# Shield_Amir_3xA4988_V_2.net
KiCad netlist of a schematic drawn in EasyEDA
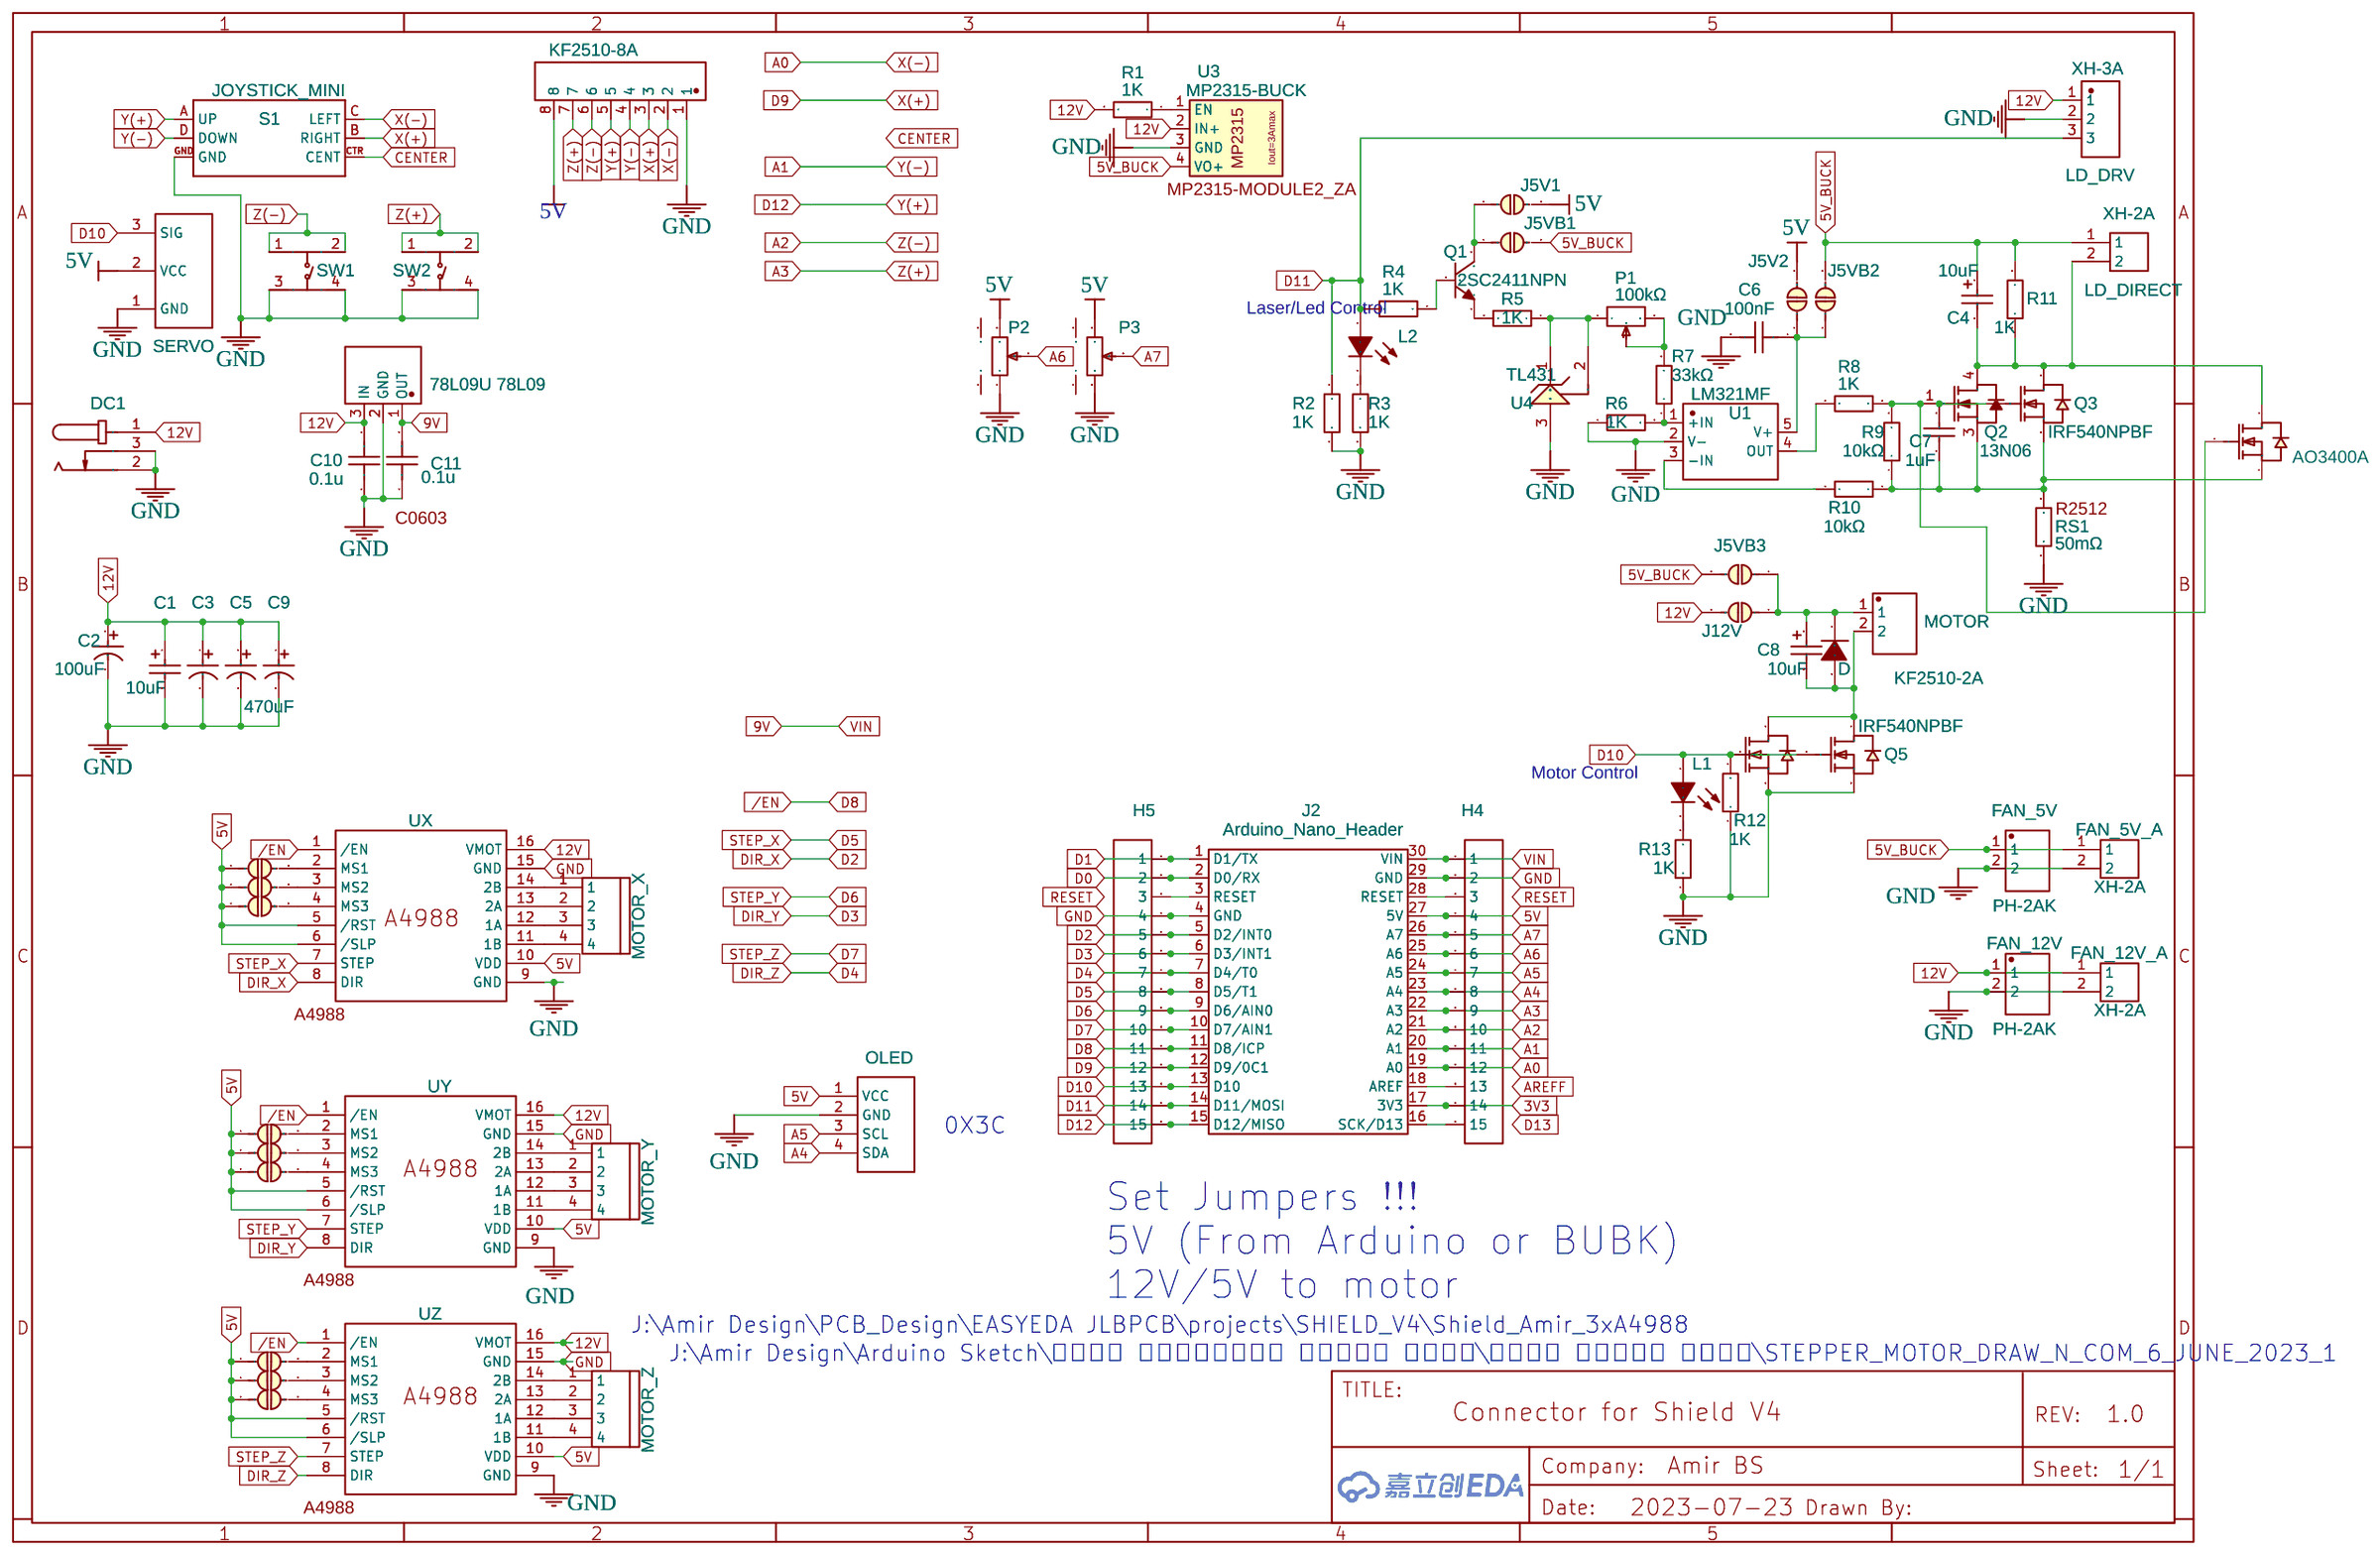
[diagram p0: schematic sheet]

(export (version "E")
  (design (tool "Eeschema 10.0.6"))
  (components
    (comp (ref "C1")
      (value "10uF")
      (fields (field (name "Manufacturer Part") "TAJA106K016RNJ") (field (name "Manufacturer") "Kyocera AVX"))
      (libsource (lib "") (part "TAJA106K016RNJ"))
    )
    (comp (ref "C2")
      (value "100uF")
      (fields
        (field (name "Manufacturer Part") "KM107M035E11RR0VH2FP0")
        (field (name "Manufacturer") "CX(承兴)")
      )
      (libsource (lib "") (part "100uF 35V 6.3*11"))
    )
    (comp (ref "C3")
      (value "470uF")
      (fields
        (field (name "Manufacturer Part") "GR477M025F12RR0VH4FP0")
        (field (name "Manufacturer") "CX(承兴)")
      )
      (libsource (lib "") (part "470uF 25V 8*12Black high frequency"))
    )
    (comp (ref "C4")
      (value "10uF")
      (fields (field (name "Manufacturer Part") "TAJA106K016RNJ") (field (name "Manufacturer") "Kyocera AVX"))
      (libsource (lib "") (part "TAJA106K016RNJ"))
    )
    (comp (ref "C5")
      (value "470uF")
      (fields
        (field (name "Manufacturer Part") "GR477M025F12RR0VH4FP0")
        (field (name "Manufacturer") "CX(承兴)")
      )
      (libsource (lib "") (part "470uF 25V 8*12Black high frequency"))
    )
    (comp (ref "C6")
      (value "100nF")
      (fields
        (field (name "BOM_Manufacturer Part") "CC0603KRX7R9BB104")
        (field (name "BOM_Supplier Part") "C14663")
      )
      (libsource (lib "") (part "CC0603KRX7R9BB104"))
    )
    (comp (ref "C7")
      (value "1uF")
      (fields
        (field (name "Manufacturer Part") "CL10A105KB8NNNC")
        (field (name "Manufacturer") "SAMSUNG(三星)")
      )
      (libsource (lib "") (part "CL10A105KB8NNNC"))
    )
    (comp (ref "C8")
      (value "10uF")
      (fields (field (name "Manufacturer Part") "TAJA106K016RNJ") (field (name "Manufacturer") "Kyocera AVX"))
      (libsource (lib "") (part "TAJA106K016RNJ"))
    )
    (comp (ref "C9")
      (value "470uF")
      (fields
        (field (name "Manufacturer Part") "GR477M025F12RR0VH4FP0")
        (field (name "Manufacturer") "CX(承兴)")
      )
      (libsource (lib "") (part "470uF 25V 8*12Black high frequency"))
    )
    (comp (ref "C10") (value "0.1u") (libsource (lib "") (part "C_0603_US")))
    (comp (ref "C11") (value "0.1u") (libsource (lib "") (part "C_0603_US_1")))
    (comp (ref "CN2")
      (value "KF2510-8A")
      (fields (field (name "Manufacturer Part") "2510-8A") (field (name "Manufacturer") "BOOMELE(博穆精密)"))
      (libsource (lib "") (part "KF2510-8A"))
    )
    (comp (ref "D")
      (value "1N4007")
      (fields (field (name "BOM_Manufacturer Part") "1N4007F") (field (name "BOM_Supplier Part") "C110856"))
      (libsource (lib "") (part "1N4007F"))
    )
    (comp (ref "DC1")
      (value "DC")
      (fields
        (field (name "BOM_Manufacturer Part") "DC005-2.0MM")
        (field (name "BOM_Supplier Part") "C111567")
      )
      (libsource (lib "") (part "DC005-2.0MM"))
    )
    (comp (ref "FAN_5V")
      (value "PH-2AK")
      (fields (field (name "BOM_Supplier Part") "C8886"))
      (libsource (lib "") (part "PH-2AK_1"))
    )
    (comp (ref "FAN_5V_A")
      (value "XH-2A")
      (fields (field (name "Manufacturer") "BOOMELE(博穆精密)"))
      (libsource (lib "") (part "XH-2A"))
    )
    (comp (ref "FAN_12V")
      (value "PH-2AK")
      (fields (field (name "BOM_Supplier Part") "C8886"))
      (libsource (lib "") (part "PH-2AK"))
    )
    (comp (ref "FAN_12V_A")
      (value "XH-2A")
      (fields (field (name "Manufacturer") "BOOMELE(博穆精密)"))
      (libsource (lib "") (part "XH-2A_1"))
    )
    (comp (ref "H4")
      (value "HDR-F-2.54_1x15")
      (fields (field (name "BOM_Supplier Part") "C124408"))
      (libsource (lib "") (part "HDR-F-2.54_1x15_1"))
    )
    (comp (ref "H5")
      (value "HDR-F-2.54_1x15")
      (fields (field (name "BOM_Supplier Part") "C124408"))
      (libsource (lib "") (part "HDR-F-2.54_1x15"))
    )
    (comp (ref "J2") (value "Arduino_Nano_Header") (libsource (lib "") (part "Arduino_Nano_Header")))
    (comp (ref "J5V1") (value "JUMPER-SMT_2") (libsource (lib "") (part "JUMPER-SMT_2_1")))
    (comp (ref "J5V2") (value "JUMPER-SMT_2") (libsource (lib "") (part "JUMPER-SMT_2_4")))
    (comp (ref "J5VB1") (value "JUMPER-SMT_2") (libsource (lib "") (part "JUMPER-SMT_2_5")))
    (comp (ref "J5VB2") (value "JUMPER-SMT_2") (libsource (lib "") (part "JUMPER-SMT_2_8")))
    (comp (ref "J5VB3") (value "JUMPER-SMT_2") (libsource (lib "") (part "JUMPER-SMT_2_7")))
    (comp (ref "J12V") (value "JUMPER-SMT_2") (libsource (lib "") (part "JUMPER-SMT_2_2")))
    (comp (ref "JX1") (value "JUMPER-SMT_2") (libsource (lib "") (part "JUMPER-SMT_2_3")))
    (comp (ref "JX2") (value "JUMPER-SMT_2") (libsource (lib "") (part "JUMPER-SMT_2_3")))
    (comp (ref "JX3") (value "JUMPER-SMT_2") (libsource (lib "") (part "JUMPER-SMT_2_3")))
    (comp (ref "JY1") (value "JUMPER-SMT_2") (libsource (lib "") (part "JUMPER-SMT_2_6")))
    (comp (ref "JY2") (value "JUMPER-SMT_2") (libsource (lib "") (part "JUMPER-SMT_2_6")))
    (comp (ref "JY3") (value "JUMPER-SMT_2") (libsource (lib "") (part "JUMPER-SMT_2_6")))
    (comp (ref "JZ1") (value "JUMPER-SMT_2") (libsource (lib "") (part "JUMPER-SMT_2")))
    (comp (ref "JZ2") (value "JUMPER-SMT_2") (libsource (lib "") (part "JUMPER-SMT_2")))
    (comp (ref "JZ3") (value "JUMPER-SMT_2") (libsource (lib "") (part "JUMPER-SMT_2")))
    (comp (ref "L1")
      (value "LED")
      (fields
        (field (name "BOM_Manufacturer Part") "19-217/BHC-ZL1M2RY/3T")
        (field (name "BOM_Supplier Part") "C72041")
      )
      (libsource (lib "") (part "19-217/BHC-ZL1M2RY/3T"))
    )
    (comp (ref "L2")
      (value "LED")
      (fields
        (field (name "BOM_Manufacturer Part") "19-217/BHC-ZL1M2RY/3T")
        (field (name "BOM_Supplier Part") "C72041")
      )
      (libsource (lib "") (part "19-217/BHC-ZL1M2RY/3T"))
    )
    (comp (ref "LD_DIRECT")
      (value "XH-2A")
      (fields (field (name "Manufacturer") "BOOMELE(博穆精密)"))
      (libsource (lib "") (part "XH-2A_2"))
    )
    (comp (ref "LD_DRV")
      (value "XH-3A")
      (fields (field (name "Manufacturer") "HCTL(华灿天禄)"))
      (libsource (lib "") (part "XH-3A_C2908601"))
    )
    (comp (ref "MOTOR")
      (value "KF2510-2A")
      (fields (field (name "BOM_Supplier Part") "C27543"))
      (libsource (lib "") (part "KF2510-2A"))
    )
    (comp (ref "MOTOR_X")
      (value "XH2.54-4AW")
      (fields (field (name "Manufacturer Part") "XH-4AW") (field (name "Manufacturer") "BOOMELE(博穆精密)"))
      (libsource (lib "") (part "XH2.54-4AW_2"))
    )
    (comp (ref "MOTOR_Y")
      (value "XH2.54-4AW")
      (fields (field (name "Manufacturer Part") "XH-4AW") (field (name "Manufacturer") "BOOMELE(博穆精密)"))
      (libsource (lib "") (part "XH2.54-4AW"))
    )
    (comp (ref "MOTOR_Z")
      (value "XH2.54-4AW")
      (fields (field (name "Manufacturer Part") "XH-4AW") (field (name "Manufacturer") "BOOMELE(博穆精密)"))
      (libsource (lib "") (part "XH2.54-4AW_1"))
    )
    (comp (ref "OLED")
      (value "1.3 inch OLED SSH1106 I2C 128x64 copy")
      (libsource (lib "") (part "1.3 inch OLED SSH1106 I2C 128x64 copy"))
    )
    (comp (ref "P1")
      (value "100kΩ")
      (fields (field (name "Manufacturer Part") "3296W-1-104LF") (field (name "Manufacturer") "BOURNS"))
      (libsource (lib "") (part "3296W-1-104LF"))
    )
    (comp (ref "P2")
      (value "长柄旋转电位器")
      (fields (field (name "BOM_Supplier Part") "C2874842"))
      (libsource (lib "") (part "长柄旋转电位器"))
    )
    (comp (ref "P3")
      (value "长柄旋转电位器")
      (fields (field (name "BOM_Supplier Part") "C2874842"))
      (libsource (lib "") (part "长柄旋转电位器"))
    )
    (comp (ref "Q1")
      (value "2SC2411NPN")
      (fields (field (name "Manufacturer Part") "2SC2411KT146R") (field (name "Manufacturer") "ROHM(罗姆)"))
      (libsource (lib "") (part "2SC2411KT146R"))
    )
    (comp (ref "Q2")
      (value "13N06")
      (fields (field (name "Manufacturer Part") "FQD13N06LTM") (field (name "Manufacturer") "onsemi(安森美)"))
      (libsource (lib "") (part "FQD13N06LTM"))
    )
    (comp (ref "Q3")
      (value "IRF540NPBF")
      (fields (field (name "Manufacturer") "Infineon(英飞凌)"))
      (libsource (lib "") (part "IRF540NPBF"))
    )
    (comp (ref "Q4")
      (value "Q")
      (fields (field (name "BOM_Manufacturer Part") "JSM2302") (field (name "BOM_Supplier Part") "C916403"))
      (libsource (lib "") (part "JSM2302"))
    )
    (comp (ref "Q5")
      (value "IRF540NPBF")
      (fields (field (name "Manufacturer") "Infineon(英飞凌)"))
      (libsource (lib "") (part "IRF540NPBF"))
    )
    (comp (ref "Q6")
      (value "AO3400A")
      (fields (field (name "Manufacturer") "AOS"))
      (libsource (lib "") (part "AO3400A"))
    )
    (comp (ref "R1")
      (value "1K")
      (fields
        (field (name "BOM_Manufacturer Part") "0603WAF1001T5E")
        (field (name "BOM_Supplier Part") "C21190")
      )
      (libsource (lib "") (part "0603WAF1001T5E_3"))
    )
    (comp (ref "R2")
      (value "1K")
      (fields
        (field (name "BOM_Manufacturer Part") "0603WAF1001T5E")
        (field (name "BOM_Supplier Part") "C21190")
      )
      (libsource (lib "") (part "0603WAF1001T5E_1"))
    )
    (comp (ref "R3")
      (value "1K")
      (fields
        (field (name "BOM_Manufacturer Part") "0603WAF1001T5E")
        (field (name "BOM_Supplier Part") "C21190")
      )
      (libsource (lib "") (part "0603WAF1001T5E_1"))
    )
    (comp (ref "R4")
      (value "1K")
      (fields
        (field (name "BOM_Manufacturer Part") "0603WAF1001T5E")
        (field (name "BOM_Supplier Part") "C21190")
      )
      (libsource (lib "") (part "0603WAF1001T5E"))
    )
    (comp (ref "R5")
      (value "1K")
      (fields
        (field (name "BOM_Manufacturer Part") "0603WAF1001T5E")
        (field (name "BOM_Supplier Part") "C21190")
      )
      (libsource (lib "") (part "0603WAF1001T5E_3"))
    )
    (comp (ref "R6")
      (value "1K")
      (fields
        (field (name "BOM_Manufacturer Part") "0603WAF1001T5E")
        (field (name "BOM_Supplier Part") "C21190")
      )
      (libsource (lib "") (part "0603WAF1001T5E"))
    )
    (comp (ref "R7")
      (value "33kΩ")
      (fields
        (field (name "Manufacturer Part") "0603WAF3302T5E")
        (field (name "Manufacturer") "UNI-ROYAL(厚声)")
      )
      (libsource (lib "") (part "0603WAF3302T5E"))
    )
    (comp (ref "R8")
      (value "1K")
      (fields
        (field (name "BOM_Manufacturer Part") "0603WAF1001T5E")
        (field (name "BOM_Supplier Part") "C21190")
      )
      (libsource (lib "") (part "0603WAF1001T5E_3"))
    )
    (comp (ref "R9")
      (value "10kΩ")
      (fields
        (field (name "BOM_Manufacturer Part") "0603WAF1002T5E")
        (field (name "BOM_Supplier Part") "C25804")
      )
      (libsource (lib "") (part "0603WAF1002T5E_1"))
    )
    (comp (ref "R10")
      (value "10kΩ")
      (fields
        (field (name "BOM_Manufacturer Part") "0603WAF1002T5E")
        (field (name "BOM_Supplier Part") "C25804")
      )
      (libsource (lib "") (part "0603WAF1002T5E"))
    )
    (comp (ref "R11")
      (value "1K")
      (fields
        (field (name "BOM_Manufacturer Part") "0603WAF1001T5E")
        (field (name "BOM_Supplier Part") "C21190")
      )
      (libsource (lib "") (part "0603WAF1001T5E_2"))
    )
    (comp (ref "R12")
      (value "1K")
      (fields
        (field (name "BOM_Manufacturer Part") "0603WAF1001T5E")
        (field (name "BOM_Supplier Part") "C21190")
      )
      (libsource (lib "") (part "0603WAF1001T5E_2"))
    )
    (comp (ref "R13")
      (value "1K")
      (fields
        (field (name "BOM_Manufacturer Part") "0603WAF1001T5E")
        (field (name "BOM_Supplier Part") "C21190")
      )
      (libsource (lib "") (part "0603WAF1001T5E_2"))
    )
    (comp (ref "RS1")
      (value "50mΩ")
      (fields
        (field (name "Manufacturer Part") "CR2512FR050E04R")
        (field (name "Manufacturer") "EVER OHMS(天二科技)")
      )
      (libsource (lib "") (part "CR2512F0R05E04"))
    )
    (comp (ref "S1") (value "JOYSTICK_MINI") (libsource (lib "") (part "JOYSTICK_MINI")))
    (comp (ref "SERVO")
      (value "Servo+3d")
      (fields (field (name "BOM_Manufacturer Part") "New SchematicLib"))
      (libsource (lib "") (part "Servo+3d"))
    )
    (comp (ref "SW1")
      (value "TC-6610-7-160G")
      (fields (field (name "Manufacturer") "HCTL(华灿天禄)"))
      (libsource (lib "") (part "TC-6610-7-160G"))
    )
    (comp (ref "SW2")
      (value "TC-6610-7-160G")
      (fields (field (name "Manufacturer") "HCTL(华灿天禄)"))
      (libsource (lib "") (part "TC-6610-7-160G"))
    )
    (comp (ref "U1")
      (value "LM321MF")
      (fields (field (name "Manufacturer") "UMW(广东友台半导体)"))
      (libsource (lib "") (part "LM321MF"))
    )
    (comp (ref "U3") (value "MP2315-BUCK") (libsource (lib "") (part "MP2315-BUCK")))
    (comp (ref "U4")
      (value "TL431")
      (fields (field (name "Manufacturer Part") "TL431BIDBZR") (field (name "Manufacturer") "TI(德州仪器)"))
      (libsource (lib "") (part "TL431BIDBZR"))
    )
    (comp (ref "U5")
      (value "78L09U 78L09")
      (fields (field (name "Manufacturer") "CBI(创基)"))
      (libsource (lib "") (part "78L09U 78L09"))
    )
    (comp (ref "UX") (value "A4988") (libsource (lib "") (part "A4988")))
    (comp (ref "UY") (value "A4988") (libsource (lib "") (part "A4988_1")))
    (comp (ref "UZ") (value "A4988") (libsource (lib "") (part "A4988_2")))
  )
  (nets
    (net (code "1") (name "3V3") (class "Default")
      (node (ref "H4") (pin "14") (pinfunction "14_14") (pintype "unspecified"))
      (node (ref "J2") (pin "17") (pinfunction "3V3_17") (pintype "unspecified"))
    )
    (net (code "2") (name "5V") (class "Default")
      (node (ref "CN2") (pin "8") (pinfunction "8_8") (pintype "unspecified"))
      (node (ref "H4") (pin "4") (pinfunction "4_4") (pintype "unspecified"))
      (node (ref "J2") (pin "27") (pinfunction "5V_27") (pintype "unspecified"))
      (node (ref "J5V1") (pin "2") (pinfunction "2_2") (pintype "bidirectional"))
      (node (ref "J5V2") (pin "2") (pinfunction "2_2") (pintype "bidirectional"))
      (node (ref "JX1") (pin "1") (pinfunction "1_1") (pintype "bidirectional"))
      (node (ref "JX2") (pin "1") (pinfunction "1_1") (pintype "bidirectional"))
      (node (ref "JX3") (pin "1") (pinfunction "1_1") (pintype "bidirectional"))
      (node (ref "JY1") (pin "1") (pinfunction "1_1") (pintype "bidirectional"))
      (node (ref "JY2") (pin "1") (pinfunction "1_1") (pintype "bidirectional"))
      (node (ref "JY3") (pin "1") (pinfunction "1_1") (pintype "bidirectional"))
      (node (ref "JZ1") (pin "1") (pinfunction "1_1") (pintype "bidirectional"))
      (node (ref "JZ2") (pin "1") (pinfunction "1_1") (pintype "bidirectional"))
      (node (ref "JZ3") (pin "1") (pinfunction "1_1") (pintype "bidirectional"))
      (node (ref "OLED") (pin "1") (pinfunction "VCC_1") (pintype "passive"))
      (node (ref "P2") (pin "3") (pinfunction "3_3") (pintype "input"))
      (node (ref "P3") (pin "3") (pinfunction "3_3") (pintype "input"))
      (node (ref "SERVO") (pin "2") (pinfunction "VCC_2") (pintype "unspecified"))
      (node (ref "UX") (pin "10") (pinfunction "VDD_10") (pintype "unspecified"))
      (node (ref "UX") (pin "5") (pinfunction "/RST_5") (pintype "unspecified"))
      (node (ref "UX") (pin "6") (pinfunction "/SLP_6") (pintype "unspecified"))
      (node (ref "UY") (pin "10") (pinfunction "VDD_10") (pintype "unspecified"))
      (node (ref "UY") (pin "5") (pinfunction "/RST_5") (pintype "unspecified"))
      (node (ref "UY") (pin "6") (pinfunction "/SLP_6") (pintype "unspecified"))
      (node (ref "UZ") (pin "10") (pinfunction "VDD_10") (pintype "unspecified"))
      (node (ref "UZ") (pin "5") (pinfunction "/RST_5") (pintype "unspecified"))
      (node (ref "UZ") (pin "6") (pinfunction "/SLP_6") (pintype "unspecified"))
    )
    (net (code "3") (name "5V_BUCK") (class "Default")
      (node (ref "C4") (pin "1") (pinfunction "1_1") (pintype "input"))
      (node (ref "FAN_5V") (pin "1") (pinfunction "1_1") (pintype "unspecified"))
      (node (ref "FAN_5V_A") (pin "1") (pinfunction "1_1") (pintype "unspecified"))
      (node (ref "J5VB1") (pin "2") (pinfunction "2_2") (pintype "bidirectional"))
      (node (ref "J5VB2") (pin "2") (pinfunction "2_2") (pintype "bidirectional"))
      (node (ref "J5VB3") (pin "2") (pinfunction "2_2") (pintype "bidirectional"))
      (node (ref "LD_DIRECT") (pin "1") (pinfunction "1_1") (pintype "unspecified"))
      (node (ref "R11") (pin "2") (pinfunction "2_2") (pintype "input"))
      (node (ref "U3") (pin "4") (pinfunction "VO+_4") (pintype "unspecified"))
    )
    (net (code "4") (name "9V") (class "Default")
      (node (ref "C11") (pin "2") (pinfunction "2_2") (pintype "unspecified"))
      (node (ref "H4") (pin "1") (pinfunction "1_1") (pintype "unspecified"))
      (node (ref "J2") (pin "30") (pinfunction "VIN_30") (pintype "unspecified"))
      (node (ref "U5") (pin "1") (pinfunction "OUT_1") (pintype "unspecified"))
    )
    (net (code "5") (name "12V") (class "Default")
      (node (ref "C1") (pin "1") (pinfunction "1_1") (pintype "input"))
      (node (ref "C10") (pin "2") (pinfunction "2_2") (pintype "unspecified"))
      (node (ref "C2") (pin "1") (pinfunction "1_1") (pintype "input"))
      (node (ref "C3") (pin "1") (pinfunction "1_1") (pintype "input"))
      (node (ref "C5") (pin "1") (pinfunction "1_1") (pintype "input"))
      (node (ref "C9") (pin "1") (pinfunction "1_1") (pintype "input"))
      (node (ref "DC1") (pin "1") (pinfunction "1_1") (pintype "unspecified"))
      (node (ref "FAN_12V") (pin "1") (pinfunction "1_1") (pintype "unspecified"))
      (node (ref "FAN_12V_A") (pin "1") (pinfunction "1_1") (pintype "unspecified"))
      (node (ref "J12V") (pin "2") (pinfunction "2_2") (pintype "bidirectional"))
      (node (ref "LD_DRV") (pin "1") (pinfunction "1_1") (pintype "unspecified"))
      (node (ref "R1") (pin "2") (pinfunction "2_2") (pintype "input"))
      (node (ref "U3") (pin "2") (pinfunction "IN+_2") (pintype "unspecified"))
      (node (ref "U5") (pin "3") (pinfunction "IN_3") (pintype "unspecified"))
      (node (ref "UX") (pin "16") (pinfunction "VMOT_16") (pintype "unspecified"))
      (node (ref "UY") (pin "16") (pinfunction "VMOT_16") (pintype "unspecified"))
      (node (ref "UZ") (pin "16") (pinfunction "VMOT_16") (pintype "unspecified"))
    )
    (net (code "6") (name "A0") (class "Default")
      (node (ref "CN2") (pin "2") (pinfunction "2_2") (pintype "unspecified"))
      (node (ref "H4") (pin "12") (pinfunction "12_12") (pintype "unspecified"))
      (node (ref "J2") (pin "19") (pinfunction "A0_19") (pintype "unspecified"))
      (node (ref "S1") (pin "C") (pinfunction "LEFT_C") (pintype "unspecified"))
    )
    (net (code "7") (name "A1") (class "Default")
      (node (ref "CN2") (pin "4") (pinfunction "4_4") (pintype "unspecified"))
      (node (ref "H4") (pin "11") (pinfunction "11_11") (pintype "unspecified"))
      (node (ref "J2") (pin "20") (pinfunction "A1_20") (pintype "unspecified"))
      (node (ref "S1") (pin "D") (pinfunction "DOWN_D") (pintype "unspecified"))
    )
    (net (code "8") (name "A2") (class "Default")
      (node (ref "CN2") (pin "6") (pinfunction "6_6") (pintype "unspecified"))
      (node (ref "H4") (pin "10") (pinfunction "10_10") (pintype "unspecified"))
      (node (ref "J2") (pin "21") (pinfunction "A2_21") (pintype "unspecified"))
      (node (ref "SW1") (pin "1") (pinfunction "1_1") (pintype "unspecified"))
      (node (ref "SW1") (pin "2") (pinfunction "2_2") (pintype "unspecified"))
    )
    (net (code "9") (name "A3") (class "Default")
      (node (ref "CN2") (pin "7") (pinfunction "7_7") (pintype "unspecified"))
      (node (ref "H4") (pin "9") (pinfunction "9_9") (pintype "unspecified"))
      (node (ref "J2") (pin "22") (pinfunction "A3_22") (pintype "unspecified"))
      (node (ref "SW2") (pin "1") (pinfunction "1_1") (pintype "unspecified"))
      (node (ref "SW2") (pin "2") (pinfunction "2_2") (pintype "unspecified"))
    )
    (net (code "10") (name "A4") (class "Default")
      (node (ref "H4") (pin "8") (pinfunction "8_8") (pintype "unspecified"))
      (node (ref "J2") (pin "23") (pinfunction "A4_23") (pintype "unspecified"))
      (node (ref "OLED") (pin "4") (pinfunction "SDA_4") (pintype "bidirectional"))
    )
    (net (code "11") (name "A5") (class "Default")
      (node (ref "H4") (pin "7") (pinfunction "7_7") (pintype "unspecified"))
      (node (ref "J2") (pin "24") (pinfunction "A5_24") (pintype "unspecified"))
      (node (ref "OLED") (pin "3") (pinfunction "SCL_3") (pintype "bidirectional"))
    )
    (net (code "12") (name "A6") (class "Default")
      (node (ref "H4") (pin "6") (pinfunction "6_6") (pintype "unspecified"))
      (node (ref "J2") (pin "25") (pinfunction "A6_25") (pintype "unspecified"))
      (node (ref "P2") (pin "2") (pinfunction "2_2") (pintype "input"))
    )
    (net (code "13") (name "A7") (class "Default")
      (node (ref "H4") (pin "5") (pinfunction "5_5") (pintype "unspecified"))
      (node (ref "J2") (pin "26") (pinfunction "A7_26") (pintype "unspecified"))
      (node (ref "P3") (pin "2") (pinfunction "2_2") (pintype "input"))
    )
    (net (code "15") (name "CENTER") (class "Default")
      (node (ref "S1") (pin "CTR") (pinfunction "CENT_CTR") (pintype "unspecified"))
    )
    (net (code "16") (name "D0") (class "Default")
      (node (ref "H5") (pin "2") (pinfunction "2_2") (pintype "unspecified"))
      (node (ref "J2") (pin "2") (pinfunction "D0/RX_2") (pintype "unspecified"))
    )
    (net (code "17") (name "D1") (class "Default")
      (node (ref "H5") (pin "1") (pinfunction "1_1") (pintype "unspecified"))
      (node (ref "J2") (pin "1") (pinfunction "D1/TX_1") (pintype "unspecified"))
    )
    (net (code "18") (name "D2") (class "Default")
      (node (ref "H5") (pin "5") (pinfunction "5_5") (pintype "unspecified"))
      (node (ref "J2") (pin "5") (pinfunction "D2/INT0_5") (pintype "unspecified"))
      (node (ref "UX") (pin "8") (pinfunction "DIR_8") (pintype "unspecified"))
    )
    (net (code "19") (name "D3") (class "Default")
      (node (ref "H5") (pin "6") (pinfunction "6_6") (pintype "unspecified"))
      (node (ref "J2") (pin "6") (pinfunction "D3/INT1_6") (pintype "unspecified"))
      (node (ref "UY") (pin "8") (pinfunction "DIR_8") (pintype "unspecified"))
    )
    (net (code "20") (name "D4") (class "Default")
      (node (ref "H5") (pin "7") (pinfunction "7_7") (pintype "unspecified"))
      (node (ref "J2") (pin "7") (pinfunction "D4/T0_7") (pintype "unspecified"))
      (node (ref "UZ") (pin "8") (pinfunction "DIR_8") (pintype "unspecified"))
    )
    (net (code "21") (name "D5") (class "Default")
      (node (ref "H5") (pin "8") (pinfunction "8_8") (pintype "unspecified"))
      (node (ref "J2") (pin "8") (pinfunction "D5/T1_8") (pintype "unspecified"))
      (node (ref "UX") (pin "7") (pinfunction "STEP_7") (pintype "unspecified"))
    )
    (net (code "22") (name "D6") (class "Default")
      (node (ref "H5") (pin "9") (pinfunction "9_9") (pintype "unspecified"))
      (node (ref "J2") (pin "9") (pinfunction "D6/AIN0_9") (pintype "unspecified"))
      (node (ref "UY") (pin "7") (pinfunction "STEP_7") (pintype "unspecified"))
    )
    (net (code "23") (name "D7") (class "Default")
      (node (ref "H5") (pin "10") (pinfunction "10_10") (pintype "unspecified"))
      (node (ref "J2") (pin "10") (pinfunction "D7/AIN1_10") (pintype "unspecified"))
      (node (ref "UZ") (pin "7") (pinfunction "STEP_7") (pintype "unspecified"))
    )
    (net (code "24") (name "D8") (class "Default")
      (node (ref "H5") (pin "11") (pinfunction "11_11") (pintype "unspecified"))
      (node (ref "J2") (pin "11") (pinfunction "D8/ICP_11") (pintype "unspecified"))
      (node (ref "UX") (pin "1") (pinfunction "/EN_1") (pintype "unspecified"))
      (node (ref "UY") (pin "1") (pinfunction "/EN_1") (pintype "unspecified"))
      (node (ref "UZ") (pin "1") (pinfunction "/EN_1") (pintype "unspecified"))
    )
    (net (code "25") (name "D9") (class "Default")
      (node (ref "CN2") (pin "3") (pinfunction "3_3") (pintype "unspecified"))
      (node (ref "H5") (pin "12") (pinfunction "12_12") (pintype "unspecified"))
      (node (ref "J2") (pin "12") (pinfunction "D9/0C1_12") (pintype "unspecified"))
      (node (ref "S1") (pin "B") (pinfunction "RIGHT_B") (pintype "unspecified"))
    )
    (net (code "26") (name "D10") (class "Default")
      (node (ref "H5") (pin "13") (pinfunction "13_13") (pintype "unspecified"))
      (node (ref "J2") (pin "13") (pinfunction "D10_13") (pintype "unspecified"))
      (node (ref "L1") (pin "1") (pinfunction "A_1") (pintype "input"))
      (node (ref "Q4") (pin "1") (pinfunction "G_1") (pintype "unspecified"))
      (node (ref "Q5") (pin "1") (pinfunction "G_1") (pintype "unspecified"))
      (node (ref "R12") (pin "2") (pinfunction "2_2") (pintype "input"))
      (node (ref "SERVO") (pin "3") (pinfunction "SIG_3") (pintype "unspecified"))
    )
    (net (code "27") (name "D11") (class "Default")
      (node (ref "H5") (pin "14") (pinfunction "14_14") (pintype "unspecified"))
      (node (ref "J2") (pin "14") (pinfunction "D11/MOSI_14") (pintype "unspecified"))
      (node (ref "L2") (pin "1") (pinfunction "A_1") (pintype "input"))
      (node (ref "LD_DRV") (pin "3") (pinfunction "3_3") (pintype "unspecified"))
      (node (ref "R2") (pin "1") (pinfunction "1_1") (pintype "input"))
      (node (ref "R4") (pin "1") (pinfunction "1_1") (pintype "input"))
    )
    (net (code "28") (name "D12") (class "Default")
      (node (ref "CN2") (pin "5") (pinfunction "5_5") (pintype "unspecified"))
      (node (ref "H5") (pin "15") (pinfunction "15_15") (pintype "unspecified"))
      (node (ref "J2") (pin "15") (pinfunction "D12/MISO_15") (pintype "unspecified"))
      (node (ref "S1") (pin "A") (pinfunction "UP_A") (pintype "unspecified"))
    )
    (net (code "30") (name "GND") (class "Default")
      (node (ref "C1") (pin "2") (pinfunction "2_2") (pintype "input"))
      (node (ref "C10") (pin "1") (pinfunction "1_1") (pintype "unspecified"))
      (node (ref "C11") (pin "1") (pinfunction "1_1") (pintype "unspecified"))
      (node (ref "C2") (pin "2") (pinfunction "2_2") (pintype "input"))
      (node (ref "C3") (pin "2") (pinfunction "2_2") (pintype "input"))
      (node (ref "C5") (pin "2") (pinfunction "2_2") (pintype "input"))
      (node (ref "C6") (pin "2") (pinfunction "2_2") (pintype "unspecified"))
      (node (ref "C9") (pin "2") (pinfunction "2_2") (pintype "input"))
      (node (ref "CN2") (pin "1") (pinfunction "1_1") (pintype "unspecified"))
      (node (ref "DC1") (pin "2") (pinfunction "2_2") (pintype "unspecified"))
      (node (ref "DC1") (pin "3") (pinfunction "3_3") (pintype "unspecified"))
      (node (ref "FAN_12V") (pin "2") (pinfunction "2_2") (pintype "unspecified"))
      (node (ref "FAN_12V_A") (pin "2") (pinfunction "2_2") (pintype "unspecified"))
      (node (ref "FAN_5V") (pin "2") (pinfunction "2_2") (pintype "unspecified"))
      (node (ref "FAN_5V_A") (pin "2") (pinfunction "2_2") (pintype "unspecified"))
      (node (ref "H4") (pin "2") (pinfunction "2_2") (pintype "unspecified"))
      (node (ref "H5") (pin "4") (pinfunction "4_4") (pintype "unspecified"))
      (node (ref "J2") (pin "29") (pinfunction "GND_29") (pintype "unspecified"))
      (node (ref "J2") (pin "4") (pinfunction "GND_4") (pintype "unspecified"))
      (node (ref "LD_DRV") (pin "2") (pinfunction "2_2") (pintype "unspecified"))
      (node (ref "OLED") (pin "2") (pinfunction "GND_2") (pintype "passive"))
      (node (ref "P2") (pin "1") (pinfunction "1_1") (pintype "input"))
      (node (ref "P3") (pin "1") (pinfunction "1_1") (pintype "input"))
      (node (ref "Q4") (pin "2") (pinfunction "S_2") (pintype "unspecified"))
      (node (ref "Q5") (pin "3") (pinfunction "S_3") (pintype "unspecified"))
      (node (ref "R12") (pin "1") (pinfunction "1_1") (pintype "input"))
      (node (ref "R13") (pin "1") (pinfunction "1_1") (pintype "input"))
      (node (ref "R2") (pin "2") (pinfunction "2_2") (pintype "input"))
      (node (ref "R3") (pin "2") (pinfunction "2_2") (pintype "input"))
      (node (ref "R6") (pin "1") (pinfunction "1_1") (pintype "input"))
      (node (ref "RS1") (pin "1") (pinfunction "1_1") (pintype "unspecified"))
      (node (ref "S1") (pin "GND") (pinfunction "GND_GND") (pintype "unspecified"))
      (node (ref "SERVO") (pin "1") (pinfunction "GND_1") (pintype "unspecified"))
      (node (ref "SW1") (pin "3") (pinfunction "3_3") (pintype "unspecified"))
      (node (ref "SW1") (pin "4") (pinfunction "4_4") (pintype "unspecified"))
      (node (ref "SW2") (pin "3") (pinfunction "3_3") (pintype "unspecified"))
      (node (ref "SW2") (pin "4") (pinfunction "4_4") (pintype "unspecified"))
      (node (ref "U1") (pin "2") (pinfunction "V-_2") (pintype "unspecified"))
      (node (ref "U3") (pin "3") (pinfunction "GND_3") (pintype "unspecified"))
      (node (ref "U4") (pin "3") (pinfunction "ANODE_3") (pintype "unspecified"))
      (node (ref "U5") (pin "2") (pinfunction "GND_2") (pintype "unspecified"))
      (node (ref "UX") (pin "15") (pinfunction "GND_15") (pintype "unspecified"))
      (node (ref "UX") (pin "9") (pinfunction "GND_9") (pintype "unspecified"))
      (node (ref "UY") (pin "15") (pinfunction "GND_15") (pintype "unspecified"))
      (node (ref "UY") (pin "9") (pinfunction "GND_9") (pintype "unspecified"))
      (node (ref "UZ") (pin "15") (pinfunction "GND_15") (pintype "unspecified"))
      (node (ref "UZ") (pin "9") (pinfunction "GND_9") (pintype "unspecified"))
    )
    (net (code "31") (name "Net-(D-A)") (class "Default")
      (node (ref "C8") (pin "2") (pinfunction "2_2") (pintype "input"))
      (node (ref "D") (pin "2") (pinfunction "A_2") (pintype "unspecified"))
      (node (ref "MOTOR") (pin "2") (pinfunction "2_2") (pintype "unspecified"))
      (node (ref "Q4") (pin "3") (pinfunction "D_3") (pintype "unspecified"))
      (node (ref "Q5") (pin "2") (pinfunction "D_2") (pintype "unspecified"))
    )
    (net (code "32") (name "Net-(D-C)") (class "Default")
      (node (ref "C8") (pin "1") (pinfunction "1_1") (pintype "input"))
      (node (ref "D") (pin "1") (pinfunction "C_1") (pintype "unspecified"))
      (node (ref "J12V") (pin "1") (pinfunction "1_1") (pintype "bidirectional"))
      (node (ref "J5VB3") (pin "1") (pinfunction "1_1") (pintype "bidirectional"))
      (node (ref "MOTOR") (pin "1") (pinfunction "1_1") (pintype "unspecified"))
    )
    (net (code "33") (name "Net-(H4-Pad3)") (class "Default")
      (node (ref "H4") (pin "3") (pinfunction "3_3") (pintype "unspecified"))
      (node (ref "J2") (pin "28") (pinfunction "RESET_28") (pintype "unspecified"))
    )
    (net (code "34") (name "Net-(H5-Pad3)") (class "Default")
      (node (ref "H5") (pin "3") (pinfunction "3_3") (pintype "unspecified"))
      (node (ref "J2") (pin "3") (pinfunction "RESET_3") (pintype "unspecified"))
    )
    (net (code "35") (name "Net-(J2-AREF)") (class "Default")
      (node (ref "H4") (pin "13") (pinfunction "13_13") (pintype "unspecified"))
      (node (ref "J2") (pin "18") (pinfunction "AREF_18") (pintype "unspecified"))
    )
    (net (code "36") (name "Net-(J2-SCK{slash}D13)") (class "Default")
      (node (ref "H4") (pin "15") (pinfunction "15_15") (pintype "unspecified"))
      (node (ref "J2") (pin "16") (pinfunction "SCK/D13_16") (pintype "unspecified"))
    )
    (net (code "37") (name "Net-(L1-C)") (class "Default")
      (node (ref "L1") (pin "2") (pinfunction "C_2") (pintype "input"))
      (node (ref "R13") (pin "2") (pinfunction "2_2") (pintype "input"))
    )
    (net (code "38") (name "Net-(L2-C)") (class "Default")
      (node (ref "L2") (pin "2") (pinfunction "C_2") (pintype "input"))
      (node (ref "R3") (pin "1") (pinfunction "1_1") (pintype "input"))
    )
    (net (code "39") (name "Net-(P1-Pad2)") (class "Default")
      (node (ref "P1") (pin "2") (pinfunction "2_2") (pintype "input"))
      (node (ref "P1") (pin "3") (pinfunction "3_3") (pintype "input"))
      (node (ref "R7") (pin "2") (pinfunction "2_2") (pintype "input"))
    )
    (net (code "40") (name "Net-(Q1-B)") (class "Default")
      (node (ref "Q1") (pin "2") (pinfunction "B_2") (pintype "unspecified"))
      (node (ref "R4") (pin "2") (pinfunction "2_2") (pintype "input"))
    )
    (net (code "41") (name "Net-(Q1-C)") (class "Default")
      (node (ref "J5V1") (pin "1") (pinfunction "1_1") (pintype "bidirectional"))
      (node (ref "J5VB1") (pin "1") (pinfunction "1_1") (pintype "bidirectional"))
      (node (ref "Q1") (pin "3") (pinfunction "C_3") (pintype "unspecified"))
    )
    (net (code "42") (name "Net-(Q1-E)") (class "Default")
      (node (ref "Q1") (pin "1") (pinfunction "E_1") (pintype "unspecified"))
      (node (ref "R5") (pin "2") (pinfunction "2_2") (pintype "input"))
    )
    (net (code "43") (name "Net-(Q2-D)") (class "Default")
      (node (ref "C4") (pin "2") (pinfunction "2_2") (pintype "input"))
      (node (ref "LD_DIRECT") (pin "2") (pinfunction "2_2") (pintype "unspecified"))
      (node (ref "Q2") (pin "4") (pinfunction "D_4") (pintype "unspecified"))
      (node (ref "Q3") (pin "2") (pinfunction "D_2") (pintype "unspecified"))
      (node (ref "Q6") (pin "3") (pinfunction "D_3") (pintype "unspecified"))
      (node (ref "R11") (pin "1") (pinfunction "1_1") (pintype "input"))
    )
    (net (code "44") (name "Net-(Q2-G)") (class "Default")
      (node (ref "C7") (pin "2") (pinfunction "2_2") (pintype "input"))
      (node (ref "Q2") (pin "1") (pinfunction "G_1") (pintype "unspecified"))
      (node (ref "Q3") (pin "1") (pinfunction "G_1") (pintype "unspecified"))
      (node (ref "Q6") (pin "1") (pinfunction "G_1") (pintype "unspecified"))
      (node (ref "R8") (pin "1") (pinfunction "1_1") (pintype "input"))
      (node (ref "R9") (pin "2") (pinfunction "2_2") (pintype "input"))
    )
    (net (code "45") (name "Net-(Q2-S)") (class "Default")
      (node (ref "C7") (pin "1") (pinfunction "1_1") (pintype "input"))
      (node (ref "Q2") (pin "3") (pinfunction "S_3") (pintype "unspecified"))
      (node (ref "Q3") (pin "3") (pinfunction "S_3") (pintype "unspecified"))
      (node (ref "Q6") (pin "2") (pinfunction "S_2") (pintype "unspecified"))
      (node (ref "R10") (pin "1") (pinfunction "1_1") (pintype "input"))
      (node (ref "R9") (pin "1") (pinfunction "1_1") (pintype "input"))
      (node (ref "RS1") (pin "2") (pinfunction "2_2") (pintype "unspecified"))
    )
    (net (code "46") (name "Net-(U1-+IN)") (class "Default")
      (node (ref "R6") (pin "2") (pinfunction "2_2") (pintype "input"))
      (node (ref "R7") (pin "1") (pinfunction "1_1") (pintype "input"))
      (node (ref "U1") (pin "1") (pinfunction "+IN_1") (pintype "unspecified"))
    )
    (net (code "47") (name "Net-(U1--IN)") (class "Default")
      (node (ref "R10") (pin "2") (pinfunction "2_2") (pintype "input"))
      (node (ref "U1") (pin "3") (pinfunction "-IN_3") (pintype "unspecified"))
    )
    (net (code "48") (name "Net-(U1-OUT)") (class "Default")
      (node (ref "R8") (pin "2") (pinfunction "2_2") (pintype "input"))
      (node (ref "U1") (pin "4") (pinfunction "OUT_4") (pintype "unspecified"))
    )
    (net (code "49") (name "Net-(U1-V+)") (class "Default")
      (node (ref "C6") (pin "1") (pinfunction "1_1") (pintype "unspecified"))
      (node (ref "J5V2") (pin "1") (pinfunction "1_1") (pintype "bidirectional"))
      (node (ref "J5VB2") (pin "1") (pinfunction "1_1") (pintype "bidirectional"))
      (node (ref "U1") (pin "5") (pinfunction "V+_5") (pintype "unspecified"))
    )
    (net (code "50") (name "Net-(U3-EN)") (class "Default")
      (node (ref "R1") (pin "1") (pinfunction "1_1") (pintype "input"))
      (node (ref "U3") (pin "1") (pinfunction "EN_1") (pintype "unspecified"))
    )
    (net (code "51") (name "Net-(U4-CATHODE)") (class "Default")
      (node (ref "P1") (pin "1") (pinfunction "1_1") (pintype "input"))
      (node (ref "R5") (pin "1") (pinfunction "1_1") (pintype "input"))
      (node (ref "U4") (pin "1") (pinfunction "CATHODE_1") (pintype "unspecified"))
      (node (ref "U4") (pin "2") (pinfunction "REF_2") (pintype "unspecified"))
    )
    (net (code "52") (name "Net-(UX-1A)") (class "Default")
      (node (ref "MOTOR_X") (pin "3") (pinfunction "3_3") (pintype "unspecified"))
      (node (ref "UX") (pin "12") (pinfunction "1A_12") (pintype "unspecified"))
    )
    (net (code "53") (name "Net-(UX-1B)") (class "Default")
      (node (ref "MOTOR_X") (pin "4") (pinfunction "4_4") (pintype "unspecified"))
      (node (ref "UX") (pin "11") (pinfunction "1B_11") (pintype "unspecified"))
    )
    (net (code "54") (name "Net-(UX-2A)") (class "Default")
      (node (ref "MOTOR_X") (pin "2") (pinfunction "2_2") (pintype "unspecified"))
      (node (ref "UX") (pin "13") (pinfunction "2A_13") (pintype "unspecified"))
    )
    (net (code "55") (name "Net-(UX-2B)") (class "Default")
      (node (ref "MOTOR_X") (pin "1") (pinfunction "1_1") (pintype "unspecified"))
      (node (ref "UX") (pin "14") (pinfunction "2B_14") (pintype "unspecified"))
    )
    (net (code "56") (name "Net-(UX-MS1)") (class "Default")
      (node (ref "JX1") (pin "2") (pinfunction "2_2") (pintype "bidirectional"))
      (node (ref "UX") (pin "2") (pinfunction "MS1_2") (pintype "unspecified"))
    )
    (net (code "57") (name "Net-(UX-MS2)") (class "Default")
      (node (ref "JX2") (pin "2") (pinfunction "2_2") (pintype "bidirectional"))
      (node (ref "UX") (pin "3") (pinfunction "MS2_3") (pintype "unspecified"))
    )
    (net (code "58") (name "Net-(UX-MS3)") (class "Default")
      (node (ref "JX3") (pin "2") (pinfunction "2_2") (pintype "bidirectional"))
      (node (ref "UX") (pin "4") (pinfunction "MS3_4") (pintype "unspecified"))
    )
    (net (code "59") (name "Net-(UY-1A)") (class "Default")
      (node (ref "MOTOR_Y") (pin "3") (pinfunction "3_3") (pintype "unspecified"))
      (node (ref "UY") (pin "12") (pinfunction "1A_12") (pintype "unspecified"))
    )
    (net (code "60") (name "Net-(UY-1B)") (class "Default")
      (node (ref "MOTOR_Y") (pin "4") (pinfunction "4_4") (pintype "unspecified"))
      (node (ref "UY") (pin "11") (pinfunction "1B_11") (pintype "unspecified"))
    )
    (net (code "61") (name "Net-(UY-2A)") (class "Default")
      (node (ref "MOTOR_Y") (pin "2") (pinfunction "2_2") (pintype "unspecified"))
      (node (ref "UY") (pin "13") (pinfunction "2A_13") (pintype "unspecified"))
    )
    (net (code "62") (name "Net-(UY-2B)") (class "Default")
      (node (ref "MOTOR_Y") (pin "1") (pinfunction "1_1") (pintype "unspecified"))
      (node (ref "UY") (pin "14") (pinfunction "2B_14") (pintype "unspecified"))
    )
    (net (code "63") (name "Net-(UY-MS1)") (class "Default")
      (node (ref "JY1") (pin "2") (pinfunction "2_2") (pintype "bidirectional"))
      (node (ref "UY") (pin "2") (pinfunction "MS1_2") (pintype "unspecified"))
    )
    (net (code "64") (name "Net-(UY-MS2)") (class "Default")
      (node (ref "JY2") (pin "2") (pinfunction "2_2") (pintype "bidirectional"))
      (node (ref "UY") (pin "3") (pinfunction "MS2_3") (pintype "unspecified"))
    )
    (net (code "65") (name "Net-(UY-MS3)") (class "Default")
      (node (ref "JY3") (pin "2") (pinfunction "2_2") (pintype "bidirectional"))
      (node (ref "UY") (pin "4") (pinfunction "MS3_4") (pintype "unspecified"))
    )
    (net (code "66") (name "Net-(UZ-1A)") (class "Default")
      (node (ref "MOTOR_Z") (pin "3") (pinfunction "3_3") (pintype "unspecified"))
      (node (ref "UZ") (pin "12") (pinfunction "1A_12") (pintype "unspecified"))
    )
    (net (code "67") (name "Net-(UZ-1B)") (class "Default")
      (node (ref "MOTOR_Z") (pin "4") (pinfunction "4_4") (pintype "unspecified"))
      (node (ref "UZ") (pin "11") (pinfunction "1B_11") (pintype "unspecified"))
    )
    (net (code "68") (name "Net-(UZ-2A)") (class "Default")
      (node (ref "MOTOR_Z") (pin "2") (pinfunction "2_2") (pintype "unspecified"))
      (node (ref "UZ") (pin "13") (pinfunction "2A_13") (pintype "unspecified"))
    )
    (net (code "69") (name "Net-(UZ-2B)") (class "Default")
      (node (ref "MOTOR_Z") (pin "1") (pinfunction "1_1") (pintype "unspecified"))
      (node (ref "UZ") (pin "14") (pinfunction "2B_14") (pintype "unspecified"))
    )
    (net (code "70") (name "Net-(UZ-MS1)") (class "Default")
      (node (ref "JZ1") (pin "2") (pinfunction "2_2") (pintype "bidirectional"))
      (node (ref "UZ") (pin "2") (pinfunction "MS1_2") (pintype "unspecified"))
    )
    (net (code "71") (name "Net-(UZ-MS2)") (class "Default")
      (node (ref "JZ2") (pin "2") (pinfunction "2_2") (pintype "bidirectional"))
      (node (ref "UZ") (pin "3") (pinfunction "MS2_3") (pintype "unspecified"))
    )
    (net (code "72") (name "Net-(UZ-MS3)") (class "Default")
      (node (ref "JZ3") (pin "2") (pinfunction "2_2") (pintype "bidirectional"))
      (node (ref "UZ") (pin "4") (pinfunction "MS3_4") (pintype "unspecified"))
    )
    (net (code "74") (name "unconnected-(P2-Pad4)") (class "Default")
      (node (ref "P2") (pin "4") (pinfunction "4_4") (pintype "input"))
    )
    (net (code "75") (name "unconnected-(P2-Pad5)") (class "Default")
      (node (ref "P2") (pin "5") (pinfunction "5_5") (pintype "input"))
    )
    (net (code "76") (name "unconnected-(P3-Pad4)") (class "Default")
      (node (ref "P3") (pin "4") (pinfunction "4_4") (pintype "input"))
    )
    (net (code "77") (name "unconnected-(P3-Pad5)") (class "Default")
      (node (ref "P3") (pin "5") (pinfunction "5_5") (pintype "input"))
    )
  )
)
